# STM_MCU.net
KiCad netlist of a schematic drawn in Altium Designer
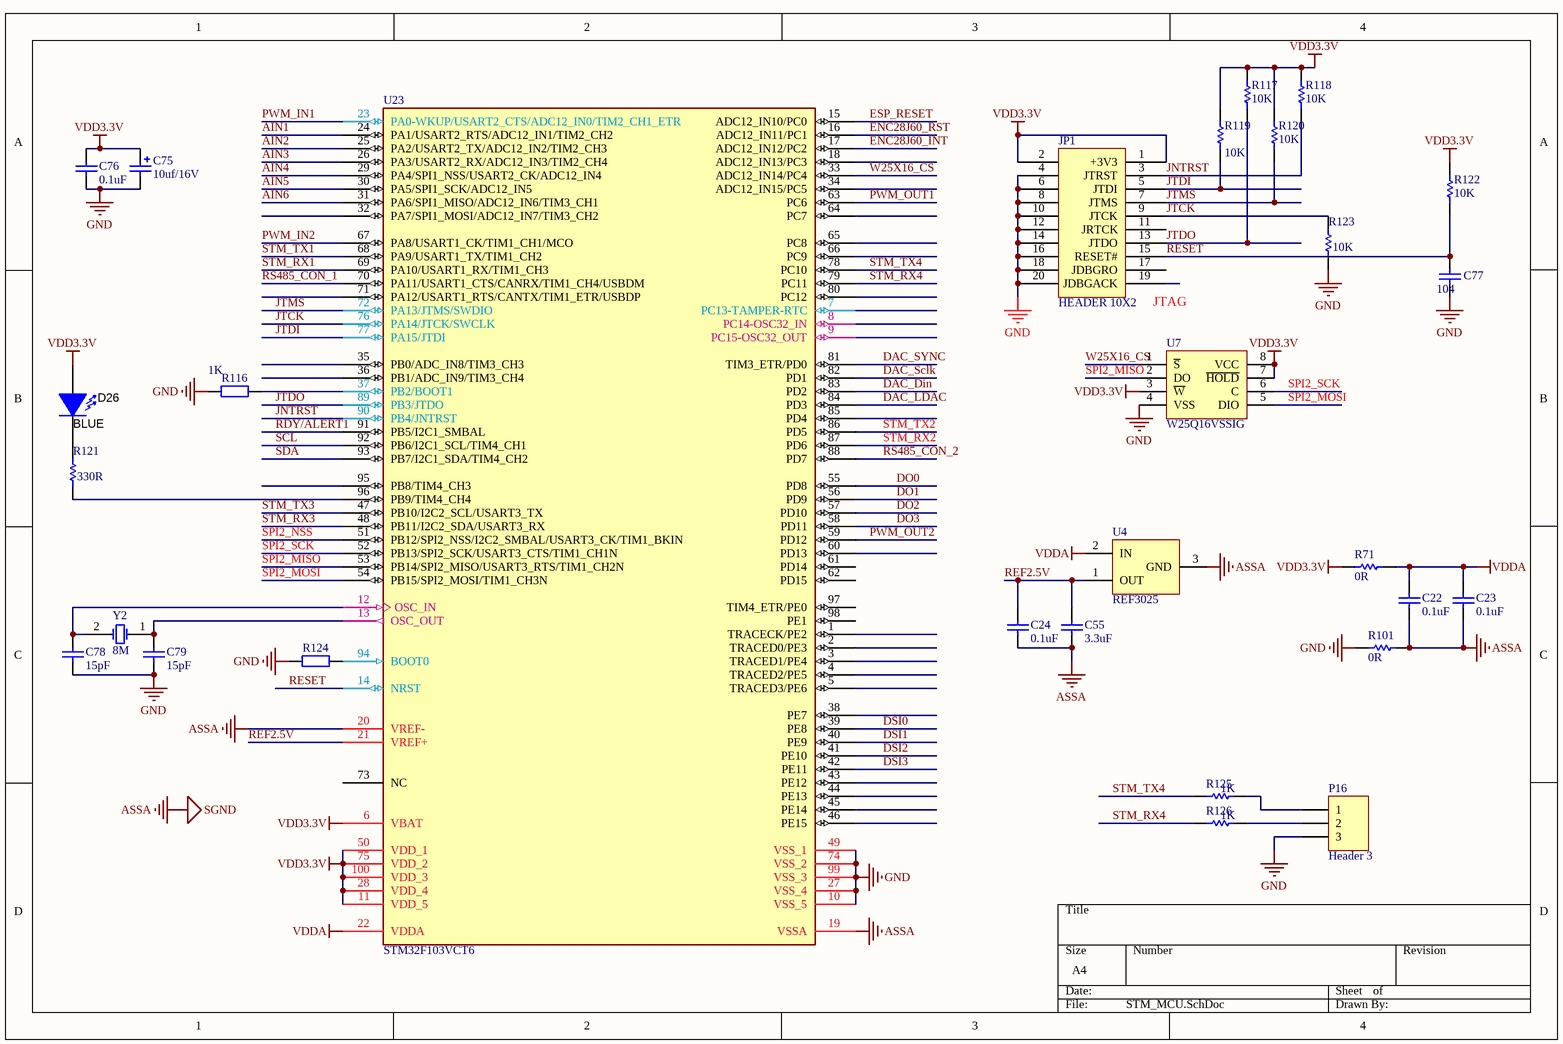
[diagram p0: STM_MCU.SchDoc]

(export (version "E")
  (design (tool "Eeschema 10.0.6"))
  (components
    (comp (ref "C22")
      (value "0.1uF")
      (footprint "C0805")
      (description "Capacitor")
      (fields (field (name "Comment") "Cap") (field (name "PUBLISHER") "Altium Limited"))
      (libsource (lib "main board") (part "Cap_2"))
    )
    (comp (ref "C23")
      (value "0.1uF")
      (footprint "C0805")
      (description "Capacitor")
      (fields (field (name "Comment") "Cap") (field (name "PUBLISHER") "Altium Limited"))
      (libsource (lib "main board") (part "Cap_2"))
    )
    (comp (ref "C24")
      (value "0.1uF")
      (footprint "C0805")
      (description "Capacitor")
      (fields (field (name "PUBLISHER") "Altium Limited"))
      (libsource (lib "Miscellaneous Devices") (part "Cap"))
    )
    (comp (ref "C55")
      (value "3.3uF")
      (footprint "C0805")
      (description "Capacitor")
      (fields (field (name "PUBLISHER") "Altium Limited"))
      (libsource (lib "Miscellaneous Devices") (part "Cap"))
    )
    (comp (ref "C75")
      (value "10uf/16V")
      (footprint "C3216")
      (description "Polarized Capacitor (Axial)")
      (fields (field (name "PUBLISHER") "Altium Limited"))
      (libsource (lib "Miscellaneous Devices") (part "Cap Pol2"))
    )
    (comp (ref "C76")
      (value "0.1uF")
      (footprint "C0805")
      (description "Capacitor")
      (fields (field (name "Comment") "Cap") (field (name "PUBLISHER") "Altium Limited"))
      (libsource (lib "main board") (part "Cap_2"))
    )
    (comp (ref "C77")
      (value "104")
      (footprint "C0805")
      (description "Capacitor")
      (fields (field (name "PUBLISHER") "Altium Limited"))
      (libsource (lib "main board") (part "Cap_2"))
    )
    (comp (ref "C78")
      (value "15pF")
      (footprint "C0805")
      (description "Capacitor")
      (fields (field (name "Comment") "Cap") (field (name "PUBLISHER") "Altium Limited"))
      (libsource (lib "Miscellaneous Devices") (part "Cap"))
    )
    (comp (ref "C79")
      (value "15pF")
      (footprint "C0805")
      (description "Capacitor")
      (fields (field (name "Comment") "Cap") (field (name "PUBLISHER") "Altium Limited"))
      (libsource (lib "Miscellaneous Devices") (part "Cap"))
    )
    (comp (ref "D26")
      (value "BLUE")
      (footprint "D0805")
      (description "LED, GREEN SMD")
      (fields
        (field (name "MANUFACTURER") "Rohm")
        (field (name "PARTNUMBER") "SML-P12YTT86")
        (field (name "PUBLISHER") "Texas Instruments")
      )
      (libsource (lib "REl") (part "SML-P12YTT86"))
    )
    (comp (ref "JP1")
      (value "HEADER 10X2")
      (footprint "STM32-JLINK")
      (libsource (lib "*") (part "HEADER 10X2"))
    )
    (comp (ref "P16")
      (value "Header 3")
      (footprint "HDR1X3")
      (description "Header, 3-Pin")
      (fields (field (name "PUBLISHER") "Altium Limited"))
      (libsource (lib "Miscellaneous Connectors") (part "Header 3"))
    )
    (comp (ref "R71")
      (value "0R")
      (footprint "0805")
      (description "Semiconductor Resistor")
      (fields (field (name "Comment") "Res Semi") (field (name "PUBLISHER") "Altium Limited"))
      (libsource (lib "Miscellaneous Devices") (part "Res Semi"))
    )
    (comp (ref "R101")
      (value "0R")
      (footprint "0805")
      (description "Semiconductor Resistor")
      (fields (field (name "Comment") "Res Semi") (field (name "PUBLISHER") "Altium Limited"))
      (libsource (lib "Miscellaneous Devices") (part "Res Semi"))
    )
    (comp (ref "R116")
      (value "1K")
      (footprint "0805")
      (fields (field (name "Comment") "Res2"))
      (libsource (lib "S1") (part "RES"))
    )
    (comp (ref "R117")
      (value "10K")
      (footprint "0805")
      (description "Semiconductor Resistor")
      (fields (field (name "Comment") "Res Semi") (field (name "PUBLISHER") "Altium Limited"))
      (libsource (lib "Miscellaneous Devices") (part "Res Semi"))
    )
    (comp (ref "R118")
      (value "10K")
      (footprint "0805")
      (description "Semiconductor Resistor")
      (fields (field (name "Comment") "Res Semi") (field (name "PUBLISHER") "Altium Limited"))
      (libsource (lib "Miscellaneous Devices") (part "Res Semi"))
    )
    (comp (ref "R119")
      (value "10K")
      (footprint "0805")
      (description "Semiconductor Resistor")
      (fields (field (name "Comment") "Res Semi") (field (name "PUBLISHER") "Altium Limited"))
      (libsource (lib "Miscellaneous Devices") (part "Res Semi"))
    )
    (comp (ref "R120")
      (value "10K")
      (footprint "0805")
      (description "Semiconductor Resistor")
      (fields (field (name "Comment") "Res Semi") (field (name "PUBLISHER") "Altium Limited"))
      (libsource (lib "Miscellaneous Devices") (part "Res Semi"))
    )
    (comp (ref "R121")
      (value "330R")
      (footprint "0805")
      (description "Semiconductor Resistor")
      (fields (field (name "Comment") "Res Semi") (field (name "PUBLISHER") "Altium Limited"))
      (libsource (lib "Miscellaneous Devices") (part "Res Semi"))
    )
    (comp (ref "R122")
      (value "10K")
      (footprint "0805")
      (description "Semiconductor Resistor")
      (fields (field (name "PUBLISHER") "Altium Limited"))
      (libsource (lib "Miscellaneous Devices") (part "Res Semi"))
    )
    (comp (ref "R123")
      (value "10K")
      (footprint "0805")
      (description "Semiconductor Resistor")
      (fields (field (name "Comment") "Res Semi") (field (name "PUBLISHER") "Altium Limited"))
      (libsource (lib "Miscellaneous Devices") (part "Res Semi"))
    )
    (comp (ref "R124") (value "Res2") (footprint "0805") (libsource (lib "S1") (part "RES")))
    (comp (ref "R125")
      (value "1K")
      (footprint "0805")
      (description "Resistor")
      (fields (field (name "Comment") "Res1") (field (name "PUBLISHER") "Altium Limited"))
      (libsource (lib "Miscellaneous Devices") (part "Res1"))
    )
    (comp (ref "R126")
      (value "1K")
      (footprint "0805")
      (description "Resistor")
      (fields (field (name "Comment") "Res1") (field (name "PUBLISHER") "Altium Limited"))
      (libsource (lib "Miscellaneous Devices") (part "Res1"))
    )
    (comp (ref "U4") (value "REF3025") (footprint "SOT-23") (libsource (lib "Schlib") (part "REF3012")))
    (comp (ref "U7") (value "W25Q16VSSIG") (footprint "wsop8") (libsource (lib "S1") (part "A25L080")))
    (comp (ref "U23")
      (value "STM32F103VCT6")
      (footprint "LQFP100_M")
      (description "STM32 ARM-based 32-bit MCU with 64 Kbytes Flash, 100-pin LQFP, Industrial Temperature")
      (fields (field (name "PUBLISHER") "*"))
      (libsource (lib "Microcontroller Unit") (part "STM32F103VBT6"))
    )
    (comp (ref "Y2")
      (value "XTAL")
      (footprint "CY")
      (description "Crystal Oscillator")
      (fields (field (name "ALTIUM_UNNAMED_1") "8M") (field (name "PUBLISHER") "Altium Limited"))
      (libsource (lib "Miscellaneous Devices") (part "XTAL"))
    )
  )
  (nets
    (net (code "1") (name "/AIN1") (class "Default")
      (node (ref "U23") (pin "24") (pinfunction "PA1/USART2_RTS/ADC12_IN1/TIM2_CH2_24") (pintype "bidirectional"))
    )
    (net (code "2") (name "/AIN2") (class "Default")
      (node (ref "U23") (pin "25") (pinfunction "PA2/USART2_TX/ADC12_IN2/TIM2_CH3_25") (pintype "bidirectional"))
    )
    (net (code "3") (name "/AIN3") (class "Default")
      (node (ref "U23") (pin "26") (pinfunction "PA3/USART2_RX/ADC12_IN3/TIM2_CH4_26") (pintype "bidirectional"))
    )
    (net (code "4") (name "/AIN4") (class "Default")
      (node (ref "U23") (pin "29") (pinfunction "PA4/SPI1_NSS/USART2_CK/ADC12_IN4_29") (pintype "bidirectional"))
    )
    (net (code "5") (name "/AIN5") (class "Default")
      (node (ref "U23") (pin "30") (pinfunction "PA5/SPI1_SCK/ADC12_IN5_30") (pintype "bidirectional"))
    )
    (net (code "6") (name "/AIN6") (class "Default")
      (node (ref "U23") (pin "31") (pinfunction "PA6/SPI1_MISO/ADC12_IN6/TIM3_CH1_31") (pintype "bidirectional"))
    )
    (net (code "7") (name "/DAC_Din") (class "Default")
      (node (ref "U23") (pin "83") (pinfunction "PD2_83") (pintype "bidirectional"))
    )
    (net (code "8") (name "/DAC_LDAC") (class "Default")
      (node (ref "U23") (pin "84") (pinfunction "PD3_84") (pintype "bidirectional"))
    )
    (net (code "9") (name "/DAC_SYNC") (class "Default")
      (node (ref "U23") (pin "81") (pinfunction "TIM3_ETR/PD0_81") (pintype "bidirectional"))
    )
    (net (code "10") (name "/DAC_Sclk") (class "Default")
      (node (ref "U23") (pin "82") (pinfunction "PD1_82") (pintype "bidirectional"))
    )
    (net (code "11") (name "/DO0") (class "Default")
      (node (ref "U23") (pin "55") (pinfunction "PD8_55") (pintype "bidirectional"))
    )
    (net (code "12") (name "/DO1") (class "Default")
      (node (ref "U23") (pin "56") (pinfunction "PD9_56") (pintype "bidirectional"))
    )
    (net (code "13") (name "/DO2") (class "Default")
      (node (ref "U23") (pin "57") (pinfunction "PD10_57") (pintype "bidirectional"))
    )
    (net (code "14") (name "/DO3") (class "Default")
      (node (ref "U23") (pin "58") (pinfunction "PD11_58") (pintype "bidirectional"))
    )
    (net (code "15") (name "/DSI0") (class "Default")
      (node (ref "U23") (pin "39") (pinfunction "PE8_39") (pintype "bidirectional"))
    )
    (net (code "16") (name "/DSI1") (class "Default")
      (node (ref "U23") (pin "40") (pinfunction "PE9_40") (pintype "bidirectional"))
    )
    (net (code "17") (name "/DSI2") (class "Default")
      (node (ref "U23") (pin "41") (pinfunction "PE10_41") (pintype "bidirectional"))
    )
    (net (code "18") (name "/DSI3") (class "Default")
      (node (ref "U23") (pin "42") (pinfunction "PE11_42") (pintype "bidirectional"))
    )
    (net (code "19") (name "/ENC28J60_INT") (class "Default")
      (node (ref "U23") (pin "17") (pinfunction "ADC12_IN12/PC2_17") (pintype "bidirectional"))
    )
    (net (code "20") (name "/ENC28J60_RST") (class "Default")
      (node (ref "U23") (pin "16") (pinfunction "ADC12_IN11/PC1_16") (pintype "bidirectional"))
    )
    (net (code "21") (name "/ESP_RESET") (class "Default")
      (node (ref "U23") (pin "15") (pinfunction "ADC12_IN10/PC0_15") (pintype "bidirectional"))
    )
    (net (code "22") (name "/JNTRST") (class "Default")
      (node (ref "JP1") (pin "3") (pinfunction "JTRST_3") (pintype "passive"))
      (node (ref "R118") (pin "1") (pinfunction "1_1") (pintype "passive"))
      (node (ref "U23") (pin "90") (pinfunction "PB4/JNTRST_90") (pintype "bidirectional"))
    )
    (net (code "23") (name "/JTCK") (class "Default")
      (node (ref "JP1") (pin "9") (pinfunction "JTCK_9") (pintype "passive"))
      (node (ref "R123") (pin "2") (pinfunction "2_2") (pintype "passive"))
      (node (ref "U23") (pin "76") (pinfunction "PA14/JTCK/SWCLK_76") (pintype "bidirectional"))
    )
    (net (code "24") (name "/JTDI") (class "Default")
      (node (ref "JP1") (pin "5") (pinfunction "JTDI_5") (pintype "passive"))
      (node (ref "R119") (pin "1") (pinfunction "1_1") (pintype "passive"))
      (node (ref "U23") (pin "77") (pinfunction "PA15/JTDI_77") (pintype "bidirectional"))
    )
    (net (code "25") (name "/JTDO") (class "Default")
      (node (ref "JP1") (pin "13") (pinfunction "JTDO_13") (pintype "passive"))
      (node (ref "R117") (pin "1") (pinfunction "1_1") (pintype "passive"))
      (node (ref "U23") (pin "89") (pinfunction "PB3/JTDO_89") (pintype "bidirectional"))
    )
    (net (code "26") (name "/JTMS") (class "Default")
      (node (ref "JP1") (pin "7") (pinfunction "JTMS_7") (pintype "passive"))
      (node (ref "R120") (pin "1") (pinfunction "1_1") (pintype "passive"))
      (node (ref "U23") (pin "72") (pinfunction "PA13/JTMS/SWDIO_72") (pintype "bidirectional"))
    )
    (net (code "27") (name "/PWM_IN1") (class "Default")
      (node (ref "U23") (pin "23") (pinfunction "PA0-WKUP/USART2_CTS/ADC12_IN0/TIM2_CH1_ETR_23") (pintype "bidirectional"))
    )
    (net (code "28") (name "/PWM_IN2") (class "Default")
      (node (ref "U23") (pin "67") (pinfunction "PA8/USART1_CK/TIM1_CH1/MCO_67") (pintype "bidirectional"))
    )
    (net (code "29") (name "/PWM_OUT1") (class "Default")
      (node (ref "U23") (pin "63") (pinfunction "PC6_63") (pintype "bidirectional"))
    )
    (net (code "30") (name "/PWM_OUT2") (class "Default")
      (node (ref "U23") (pin "59") (pinfunction "PD12_59") (pintype "bidirectional"))
    )
    (net (code "31") (name "/RDY{slash}ALERT1") (class "Default")
      (node (ref "U23") (pin "91") (pinfunction "PB5/I2C1_SMBAL_91") (pintype "bidirectional"))
    )
    (net (code "32") (name "/REF2.5V") (class "Default")
      (node (ref "C24") (pin "2") (pinfunction "2_2") (pintype "passive"))
      (node (ref "C55") (pin "2") (pinfunction "2_2") (pintype "passive"))
      (node (ref "U23") (pin "21") (pinfunction "VREF+_21") (pintype "power_in"))
      (node (ref "U4") (pin "1") (pinfunction "OUT_1") (pintype "passive"))
    )
    (net (code "33") (name "/RESET") (class "Default")
      (node (ref "C77") (pin "2") (pinfunction "2_2") (pintype "passive"))
      (node (ref "JP1") (pin "15") (pinfunction "RESET#_15") (pintype "passive"))
      (node (ref "R122") (pin "1") (pinfunction "1_1") (pintype "passive"))
      (node (ref "U23") (pin "14") (pinfunction "NRST_14") (pintype "bidirectional"))
    )
    (net (code "34") (name "/RS485_CON_1") (class "Default")
      (node (ref "U23") (pin "70") (pinfunction "PA11/USART1_CTS/CANRX/TIM1_CH4/USBDM_70") (pintype "bidirectional"))
    )
    (net (code "35") (name "/RS485_CON_2") (class "Default")
      (node (ref "U23") (pin "88") (pinfunction "PD7_88") (pintype "bidirectional"))
    )
    (net (code "36") (name "/SCL") (class "Default")
      (node (ref "U23") (pin "92") (pinfunction "PB6/I2C1_SCL/TIM4_CH1_92") (pintype "bidirectional"))
    )
    (net (code "37") (name "/SDA") (class "Default")
      (node (ref "U23") (pin "93") (pinfunction "PB7/I2C1_SDA/TIM4_CH2_93") (pintype "bidirectional"))
    )
    (net (code "38") (name "/SPI2_MISO") (class "Default")
      (node (ref "U23") (pin "53") (pinfunction "PB14/SPI2_MISO/USART3_RTS/TIM1_CH2N_53") (pintype "bidirectional"))
      (node (ref "U7") (pin "2") (pinfunction "DO_2") (pintype "passive"))
    )
    (net (code "39") (name "/SPI2_MOSI") (class "Default")
      (node (ref "U23") (pin "54") (pinfunction "PB15/SPI2_MOSI/TIM1_CH3N_54") (pintype "bidirectional"))
      (node (ref "U7") (pin "5") (pinfunction "DIO_5") (pintype "passive"))
    )
    (net (code "40") (name "/SPI2_NSS") (class "Default")
      (node (ref "U23") (pin "51") (pinfunction "PB12/SPI2_NSS/I2C2_SMBAL/USART3_CK/TIM1_BKIN_51") (pintype "bidirectional"))
    )
    (net (code "41") (name "/SPI2_SCK") (class "Default")
      (node (ref "U23") (pin "52") (pinfunction "PB13/SPI2_SCK/USART3_CTS/TIM1_CH1N_52") (pintype "bidirectional"))
      (node (ref "U7") (pin "6") (pinfunction "C_6") (pintype "passive"))
    )
    (net (code "42") (name "/STM_RX1") (class "Default")
      (node (ref "U23") (pin "69") (pinfunction "PA10/USART1_RX/TIM1_CH3_69") (pintype "bidirectional"))
    )
    (net (code "43") (name "/STM_RX2") (class "Default")
      (node (ref "U23") (pin "87") (pinfunction "PD6_87") (pintype "bidirectional"))
    )
    (net (code "44") (name "/STM_RX3") (class "Default")
      (node (ref "U23") (pin "48") (pinfunction "PB11/I2C2_SDA/USART3_RX_48") (pintype "bidirectional"))
    )
    (net (code "45") (name "/STM_RX4") (class "Default")
      (node (ref "R126") (pin "1") (pinfunction "1_1") (pintype "passive"))
      (node (ref "U23") (pin "79") (pinfunction "PC11_79") (pintype "bidirectional"))
    )
    (net (code "46") (name "/STM_TX1") (class "Default")
      (node (ref "U23") (pin "68") (pinfunction "PA9/USART1_TX/TIM1_CH2_68") (pintype "bidirectional"))
    )
    (net (code "47") (name "/STM_TX2") (class "Default")
      (node (ref "U23") (pin "86") (pinfunction "PD5_86") (pintype "bidirectional"))
    )
    (net (code "48") (name "/STM_TX3") (class "Default")
      (node (ref "U23") (pin "47") (pinfunction "PB10/I2C2_SCL/USART3_TX_47") (pintype "bidirectional"))
    )
    (net (code "49") (name "/STM_TX4") (class "Default")
      (node (ref "R125") (pin "1") (pinfunction "1_1") (pintype "passive"))
      (node (ref "U23") (pin "78") (pinfunction "PC10_78") (pintype "bidirectional"))
    )
    (net (code "50") (name "/W25X16_CS") (class "Default")
      (node (ref "U23") (pin "33") (pinfunction "ADC12_IN14/PC4_33") (pintype "bidirectional"))
      (node (ref "U7") (pin "1") (pinfunction "~{S}_1") (pintype "passive"))
    )
    (net (code "51") (name "ASSA") (class "Default")
      (node (ref "C22") (pin "1") (pinfunction "1_1") (pintype "passive"))
      (node (ref "C23") (pin "1") (pinfunction "1_1") (pintype "passive"))
      (node (ref "C24") (pin "1") (pinfunction "1_1") (pintype "passive"))
      (node (ref "C55") (pin "1") (pinfunction "1_1") (pintype "passive"))
      (node (ref "R101") (pin "2") (pinfunction "2_2") (pintype "passive"))
      (node (ref "U23") (pin "19") (pinfunction "VSSA_19") (pintype "power_in"))
      (node (ref "U23") (pin "20") (pinfunction "VREF-_20") (pintype "power_in"))
      (node (ref "U4") (pin "3") (pinfunction "GND_3") (pintype "passive"))
    )
    (net (code "52") (name "GND") (class "Default")
      (node (ref "C75") (pin "2") (pinfunction "2_2") (pintype "passive"))
      (node (ref "C76") (pin "1") (pinfunction "1_1") (pintype "passive"))
      (node (ref "C77") (pin "1") (pinfunction "1_1") (pintype "passive"))
      (node (ref "C78") (pin "1") (pinfunction "1_1") (pintype "passive"))
      (node (ref "C79") (pin "1") (pinfunction "1_1") (pintype "passive"))
      (node (ref "JP1") (pin "10") (pintype "passive"))
      (node (ref "JP1") (pin "12") (pintype "passive"))
      (node (ref "JP1") (pin "14") (pintype "passive"))
      (node (ref "JP1") (pin "16") (pintype "passive"))
      (node (ref "JP1") (pin "18") (pintype "passive"))
      (node (ref "JP1") (pin "20") (pintype "passive"))
      (node (ref "JP1") (pin "4") (pintype "passive"))
      (node (ref "JP1") (pin "6") (pintype "passive"))
      (node (ref "JP1") (pin "8") (pintype "passive"))
      (node (ref "P16") (pin "3") (pinfunction "3_3") (pintype "passive"))
      (node (ref "R101") (pin "1") (pinfunction "1_1") (pintype "passive"))
      (node (ref "R116") (pin "1") (pinfunction "1_1") (pintype "passive"))
      (node (ref "R123") (pin "1") (pinfunction "1_1") (pintype "passive"))
      (node (ref "R124") (pin "1") (pinfunction "1_1") (pintype "passive"))
      (node (ref "U23") (pin "10") (pinfunction "VSS_5_10") (pintype "power_in"))
      (node (ref "U23") (pin "27") (pinfunction "VSS_4_27") (pintype "power_in"))
      (node (ref "U23") (pin "49") (pinfunction "VSS_1_49") (pintype "power_in"))
      (node (ref "U23") (pin "74") (pinfunction "VSS_2_74") (pintype "power_in"))
      (node (ref "U23") (pin "99") (pinfunction "VSS_3_99") (pintype "power_in"))
      (node (ref "U7") (pin "4") (pinfunction "VSS_4") (pintype "passive"))
    )
    (net (code "53") (name "Net-(D26-K)") (class "Default")
      (node (ref "D26") (pin "2") (pinfunction "K_2") (pintype "passive"))
      (node (ref "R121") (pin "2") (pinfunction "2_2") (pintype "passive"))
    )
    (net (code "54") (name "Net-(P16-Pad1)") (class "Default")
      (node (ref "P16") (pin "1") (pinfunction "1_1") (pintype "passive"))
      (node (ref "R125") (pin "2") (pinfunction "2_2") (pintype "passive"))
    )
    (net (code "55") (name "Net-(P16-Pad2)") (class "Default")
      (node (ref "P16") (pin "2") (pinfunction "2_2") (pintype "passive"))
      (node (ref "R126") (pin "2") (pinfunction "2_2") (pintype "passive"))
    )
    (net (code "56") (name "Net-(U23-BOOT0)") (class "Default")
      (node (ref "R124") (pin "2") (pinfunction "2_2") (pintype "passive"))
      (node (ref "U23") (pin "94") (pinfunction "BOOT0_94") (pintype "input"))
    )
    (net (code "57") (name "Net-(U23-OSC_IN)") (class "Default")
      (node (ref "C78") (pin "2") (pinfunction "2_2") (pintype "passive"))
      (node (ref "U23") (pin "12") (pinfunction "OSC_IN_12") (pintype "input"))
      (node (ref "Y2") (pin "2") (pinfunction "OSC2_2") (pintype "passive"))
    )
    (net (code "58") (name "Net-(U23-OSC_OUT)") (class "Default")
      (node (ref "C79") (pin "2") (pinfunction "2_2") (pintype "passive"))
      (node (ref "U23") (pin "13") (pinfunction "OSC_OUT_13") (pintype "output"))
      (node (ref "Y2") (pin "1") (pinfunction "OSC1_1") (pintype "passive"))
    )
    (net (code "59") (name "Net-(U23-PB2{slash}BOOT1)") (class "Default")
      (node (ref "R116") (pin "2") (pinfunction "2_2") (pintype "passive"))
      (node (ref "U23") (pin "37") (pinfunction "PB2/BOOT1_37") (pintype "bidirectional"))
    )
    (net (code "60") (name "Net-(U23-PB9{slash}TIM4_CH4)") (class "Default")
      (node (ref "R121") (pin "1") (pinfunction "1_1") (pintype "passive"))
      (node (ref "U23") (pin "96") (pinfunction "PB9/TIM4_CH4_96") (pintype "bidirectional"))
    )
    (net (code "61") (name "VDD3.3V") (class "Default")
      (node (ref "C75") (pin "1") (pinfunction "1_1") (pintype "passive"))
      (node (ref "C76") (pin "2") (pinfunction "2_2") (pintype "passive"))
      (node (ref "D26") (pin "1") (pinfunction "A_1") (pintype "passive"))
      (node (ref "JP1") (pin "1") (pinfunction "+3V3_1") (pintype "passive"))
      (node (ref "JP1") (pin "2") (pintype "passive"))
      (node (ref "R117") (pin "2") (pinfunction "2_2") (pintype "passive"))
      (node (ref "R118") (pin "2") (pinfunction "2_2") (pintype "passive"))
      (node (ref "R119") (pin "2") (pinfunction "2_2") (pintype "passive"))
      (node (ref "R120") (pin "2") (pinfunction "2_2") (pintype "passive"))
      (node (ref "R122") (pin "2") (pinfunction "2_2") (pintype "passive"))
      (node (ref "R71") (pin "1") (pinfunction "1_1") (pintype "passive"))
      (node (ref "U23") (pin "100") (pinfunction "VDD_3_100") (pintype "power_in"))
      (node (ref "U23") (pin "11") (pinfunction "VDD_5_11") (pintype "power_in"))
      (node (ref "U23") (pin "28") (pinfunction "VDD_4_28") (pintype "power_in"))
      (node (ref "U23") (pin "50") (pinfunction "VDD_1_50") (pintype "power_in"))
      (node (ref "U23") (pin "6") (pinfunction "VBAT_6") (pintype "power_in"))
      (node (ref "U23") (pin "75") (pinfunction "VDD_2_75") (pintype "power_in"))
      (node (ref "U7") (pin "3") (pinfunction "~{W}_3") (pintype "passive"))
      (node (ref "U7") (pin "7") (pinfunction "~{HOLD}_7") (pintype "passive"))
      (node (ref "U7") (pin "8") (pinfunction "VCC_8") (pintype "passive"))
    )
    (net (code "62") (name "VDDA") (class "Default")
      (node (ref "C22") (pin "2") (pinfunction "2_2") (pintype "passive"))
      (node (ref "C23") (pin "2") (pinfunction "2_2") (pintype "passive"))
      (node (ref "R71") (pin "2") (pinfunction "2_2") (pintype "passive"))
      (node (ref "U23") (pin "22") (pinfunction "VDDA_22") (pintype "power_in"))
      (node (ref "U4") (pin "2") (pinfunction "IN_2") (pintype "passive"))
    )
    (net (code "63") (name "unconnected-(JP1-JDBGACK-Pad19)") (class "Default")
      (node (ref "JP1") (pin "19") (pinfunction "JDBGACK_19") (pintype "passive"))
    )
    (net (code "64") (name "unconnected-(JP1-JDBGRO-Pad17)") (class "Default")
      (node (ref "JP1") (pin "17") (pinfunction "JDBGRO_17") (pintype "passive"))
    )
    (net (code "65") (name "unconnected-(JP1-JRTCK-Pad11)") (class "Default")
      (node (ref "JP1") (pin "11") (pinfunction "JRTCK_11") (pintype "passive"))
    )
    (net (code "66") (name "unconnected-(U23-ADC12_IN13{slash}PC3-Pad18)") (class "Default")
      (node (ref "U23") (pin "18") (pinfunction "ADC12_IN13/PC3_18") (pintype "bidirectional"))
    )
    (net (code "67") (name "unconnected-(U23-ADC12_IN15{slash}PC5-Pad34)") (class "Default")
      (node (ref "U23") (pin "34") (pinfunction "ADC12_IN15/PC5_34") (pintype "bidirectional"))
    )
    (net (code "68") (name "unconnected-(U23-NC-Pad73)") (class "Default")
      (node (ref "U23") (pin "73") (pinfunction "NC_73") (pintype "tri_state"))
    )
    (net (code "69") (name "unconnected-(U23-PA7{slash}SPI1_MOSI{slash}ADC12_IN7{slash}TIM3_CH2-Pad32)") (class "Default")
      (node (ref "U23") (pin "32") (pinfunction "PA7/SPI1_MOSI/ADC12_IN7/TIM3_CH2_32") (pintype "bidirectional"))
    )
    (net (code "70") (name "unconnected-(U23-PA12{slash}USART1_RTS{slash}CANTX{slash}TIM1_ETR{slash}USBDP-Pad71)") (class "Default")
      (node (ref "U23") (pin "71") (pinfunction "PA12/USART1_RTS/CANTX/TIM1_ETR/USBDP_71") (pintype "bidirectional"))
    )
    (net (code "71") (name "unconnected-(U23-PB0{slash}ADC_IN8{slash}TIM3_CH3-Pad35)") (class "Default")
      (node (ref "U23") (pin "35") (pinfunction "PB0/ADC_IN8/TIM3_CH3_35") (pintype "bidirectional"))
    )
    (net (code "72") (name "unconnected-(U23-PB1{slash}ADC_IN9{slash}TIM3_CH4-Pad36)") (class "Default")
      (node (ref "U23") (pin "36") (pinfunction "PB1/ADC_IN9/TIM3_CH4_36") (pintype "bidirectional"))
    )
    (net (code "73") (name "unconnected-(U23-PB8{slash}TIM4_CH3-Pad95)") (class "Default")
      (node (ref "U23") (pin "95") (pinfunction "PB8/TIM4_CH3_95") (pintype "bidirectional"))
    )
    (net (code "74") (name "unconnected-(U23-PC7-Pad64)") (class "Default")
      (node (ref "U23") (pin "64") (pinfunction "PC7_64") (pintype "bidirectional"))
    )
    (net (code "75") (name "unconnected-(U23-PC8-Pad65)") (class "Default")
      (node (ref "U23") (pin "65") (pinfunction "PC8_65") (pintype "bidirectional"))
    )
    (net (code "76") (name "unconnected-(U23-PC9-Pad66)") (class "Default")
      (node (ref "U23") (pin "66") (pinfunction "PC9_66") (pintype "bidirectional"))
    )
    (net (code "77") (name "unconnected-(U23-PC12-Pad80)") (class "Default")
      (node (ref "U23") (pin "80") (pinfunction "PC12_80") (pintype "bidirectional"))
    )
    (net (code "78") (name "unconnected-(U23-PC13-TAMPER-RTC-Pad7)") (class "Default")
      (node (ref "U23") (pin "7") (pinfunction "PC13-TAMPER-RTC_7") (pintype "bidirectional"))
    )
    (net (code "79") (name "unconnected-(U23-PC14-OSC32_IN-Pad8)") (class "Default")
      (node (ref "U23") (pin "8") (pinfunction "PC14-OSC32_IN_8") (pintype "bidirectional"))
    )
    (net (code "80") (name "unconnected-(U23-PC15-OSC32_OUT-Pad9)") (class "Default")
      (node (ref "U23") (pin "9") (pinfunction "PC15-OSC32_OUT_9") (pintype "bidirectional"))
    )
    (net (code "81") (name "unconnected-(U23-PD4-Pad85)") (class "Default")
      (node (ref "U23") (pin "85") (pinfunction "PD4_85") (pintype "bidirectional"))
    )
    (net (code "82") (name "unconnected-(U23-PD13-Pad60)") (class "Default")
      (node (ref "U23") (pin "60") (pinfunction "PD13_60") (pintype "bidirectional"))
    )
    (net (code "83") (name "unconnected-(U23-PD14-Pad61)") (class "Default")
      (node (ref "U23") (pin "61") (pinfunction "PD14_61") (pintype "bidirectional"))
    )
    (net (code "84") (name "unconnected-(U23-PD15-Pad62)") (class "Default")
      (node (ref "U23") (pin "62") (pinfunction "PD15_62") (pintype "bidirectional"))
    )
    (net (code "85") (name "unconnected-(U23-PE1-Pad98)") (class "Default")
      (node (ref "U23") (pin "98") (pinfunction "PE1_98") (pintype "bidirectional"))
    )
    (net (code "86") (name "unconnected-(U23-PE7-Pad38)") (class "Default")
      (node (ref "U23") (pin "38") (pinfunction "PE7_38") (pintype "bidirectional"))
    )
    (net (code "87") (name "unconnected-(U23-PE12-Pad43)") (class "Default")
      (node (ref "U23") (pin "43") (pinfunction "PE12_43") (pintype "bidirectional"))
    )
    (net (code "88") (name "unconnected-(U23-PE13-Pad44)") (class "Default")
      (node (ref "U23") (pin "44") (pinfunction "PE13_44") (pintype "bidirectional"))
    )
    (net (code "89") (name "unconnected-(U23-PE14-Pad45)") (class "Default")
      (node (ref "U23") (pin "45") (pinfunction "PE14_45") (pintype "bidirectional"))
    )
    (net (code "90") (name "unconnected-(U23-PE15-Pad46)") (class "Default")
      (node (ref "U23") (pin "46") (pinfunction "PE15_46") (pintype "bidirectional"))
    )
    (net (code "91") (name "unconnected-(U23-TIM4_ETR{slash}PE0-Pad97)") (class "Default")
      (node (ref "U23") (pin "97") (pinfunction "TIM4_ETR/PE0_97") (pintype "bidirectional"))
    )
    (net (code "92") (name "unconnected-(U23-TRACECK{slash}PE2-Pad1)") (class "Default")
      (node (ref "U23") (pin "1") (pinfunction "TRACECK/PE2_1") (pintype "bidirectional"))
    )
    (net (code "93") (name "unconnected-(U23-TRACED0{slash}PE3-Pad2)") (class "Default")
      (node (ref "U23") (pin "2") (pinfunction "TRACED0/PE3_2") (pintype "bidirectional"))
    )
    (net (code "94") (name "unconnected-(U23-TRACED1{slash}PE4-Pad3)") (class "Default")
      (node (ref "U23") (pin "3") (pinfunction "TRACED1/PE4_3") (pintype "bidirectional"))
    )
    (net (code "95") (name "unconnected-(U23-TRACED2{slash}PE5-Pad4)") (class "Default")
      (node (ref "U23") (pin "4") (pinfunction "TRACED2/PE5_4") (pintype "bidirectional"))
    )
    (net (code "96") (name "unconnected-(U23-TRACED3{slash}PE6-Pad5)") (class "Default")
      (node (ref "U23") (pin "5") (pinfunction "TRACED3/PE6_5") (pintype "bidirectional"))
    )
  )
)
